# atx4vc.net
KiCad netlist of a schematic drawn in EAGLE
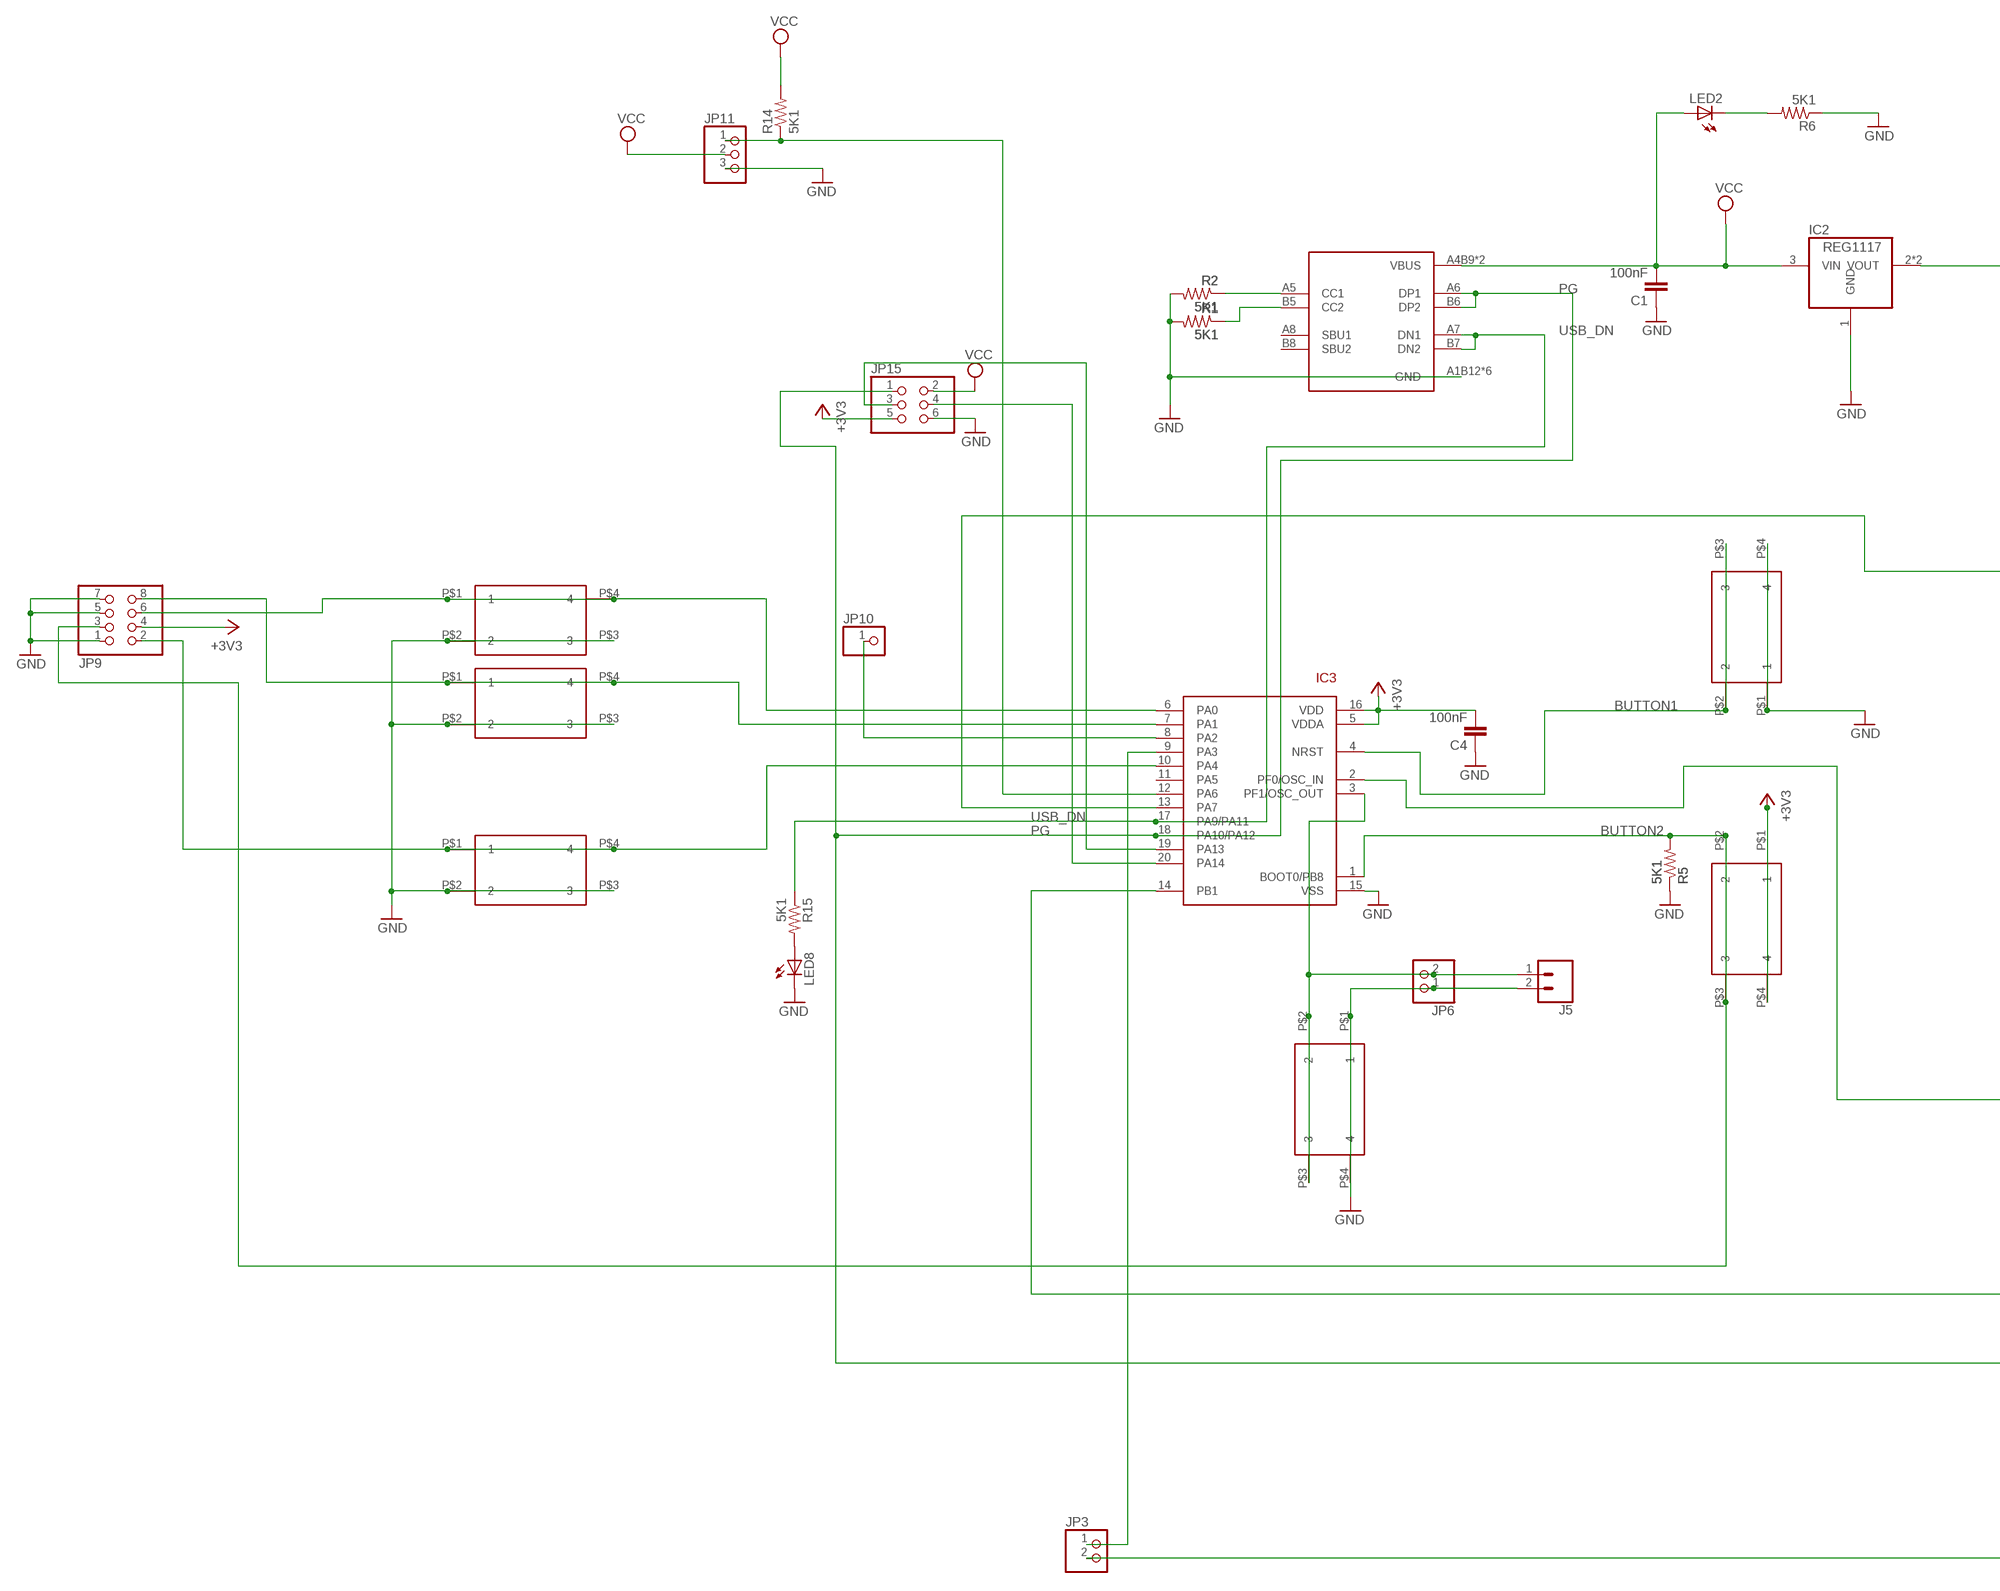
[diagram p0: schematic, sheet 1, part 1 of 2]
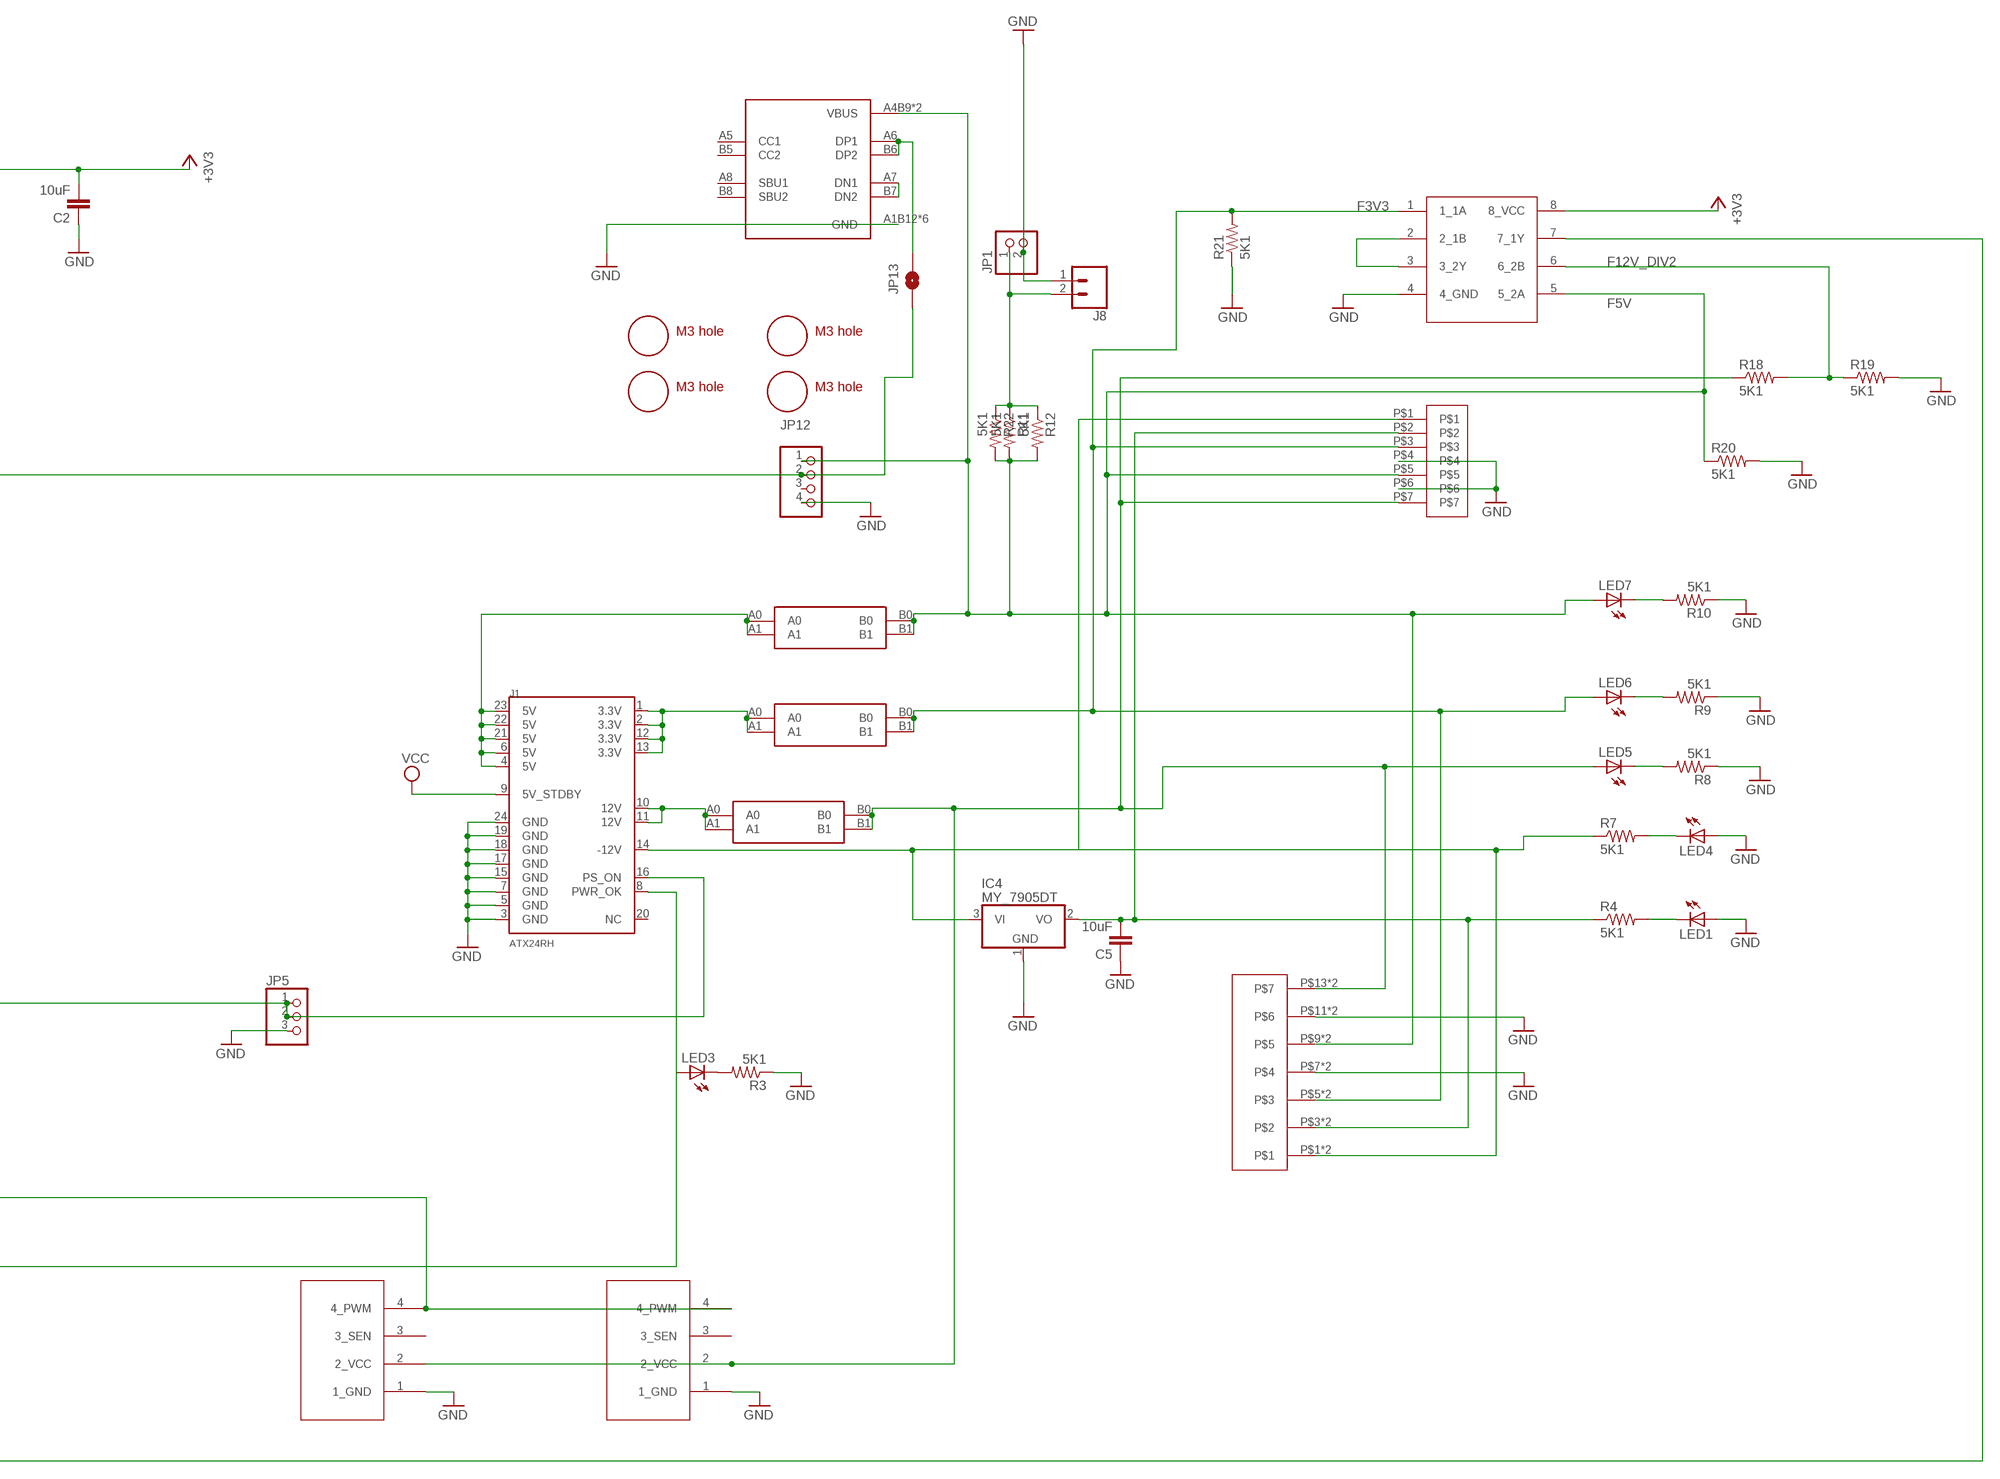
[diagram p1: schematic, sheet 1, part 2 of 2]

(export (version "E")
  (design (tool "Eeschema 10.0.6"))
  (components
    (comp (ref "C1")
      (value "100nF")
      (footprint "eagle-import:0805$1")
      (libsource (lib "eagle-import") (part "CAP0805"))
    )
    (comp (ref "C2")
      (value "10uF")
      (footprint "eagle-import:0805$1")
      (libsource (lib "eagle-import") (part "CAP0805"))
    )
    (comp (ref "C4")
      (value "100nF")
      (footprint "eagle-import:0805$1")
      (libsource (lib "eagle-import") (part "CAP0805"))
    )
    (comp (ref "C5")
      (value "10uF")
      (footprint "eagle-import:0805$1")
      (libsource (lib "eagle-import") (part "CAP0805"))
    )
    (comp (ref "IC2")
      (value "REG1117")
      (footprint "eagle-import:SOT223")
      (fields (field (name "MF") "TEXAS INSTRUMENTS") (field (name "MPN") "REG1117FAKTTT"))
      (libsource (lib "eagle-import") (part "REG1117"))
    )
    (comp (ref "IC3")
      (value "STM32F042F4")
      (footprint "eagle-import:TSSOP20")
      (libsource (lib "eagle-import") (part "STM32F042F4"))
    )
    (comp (ref "IC4")
      (value "MY_7905DT")
      (footprint "eagle-import:ADAFRUIT_TO252")
      (libsource (lib "eagle-import") (part "MY_7905DT"))
    )
    (comp (ref "J1")
      (value "ATX24RH")
      (footprint "eagle-import:ATX24_RIGHT_ANGLE")
      (libsource (lib "eagle-import") (part "ATX24RH"))
    )
    (comp (ref "J5")
      (value "CONN_023.5MM")
      (footprint "eagle-import:SCREWTERMINAL-3.5MM-2")
      (libsource (lib "eagle-import") (part "CONN_023.5MM"))
    )
    (comp (ref "J8")
      (value "CONN_023.5MM")
      (footprint "eagle-import:SCREWTERMINAL-3.5MM-2")
      (libsource (lib "eagle-import") (part "CONN_023.5MM"))
    )
    (comp (ref "JP1")
      (value "PINHD-1X2")
      (footprint "eagle-import:1X02")
      (libsource (lib "eagle-import") (part "pinhead_325_PINHD-1X2"))
    )
    (comp (ref "JP3")
      (value "PINHD-1X2")
      (footprint "eagle-import:1X02")
      (libsource (lib "eagle-import") (part "pinhead_325_PINHD-1X2"))
    )
    (comp (ref "JP5")
      (value "PINHD-1X3:1")
      (footprint "eagle-import:1X03")
      (libsource (lib "eagle-import") (part "PINHD-1X3?{colon}1"))
    )
    (comp (ref "JP6")
      (value "PINHD-1X2")
      (footprint "eagle-import:1X02")
      (libsource (lib "eagle-import") (part "PINHD-1X2"))
    )
    (comp (ref "JP8")
      (value "4PIN_FAN")
      (footprint "eagle-import:1X04")
      (libsource (lib "eagle-import") (part "4PIN_FAN"))
    )
    (comp (ref "JP9")
      (value "PINHD-2X4")
      (footprint "eagle-import:2X04")
      (libsource (lib "eagle-import") (part "PINHD-2X4"))
    )
    (comp (ref "JP10")
      (value "PINHD-1X1CB")
      (footprint "eagle-import:1X01-CLEANBIG")
      (libsource (lib "eagle-import") (part "PINHD-1X1CB"))
    )
    (comp (ref "JP11")
      (value "PINHD-1X3")
      (footprint "eagle-import:1X03")
      (libsource (lib "eagle-import") (part "PINHD-1X3"))
    )
    (comp (ref "JP12")
      (value "PINHD-1X4")
      (footprint "eagle-import:1X04")
      (libsource (lib "eagle-import") (part "PINHD-1X4"))
    )
    (comp (ref "JP13")
      (value "JUMPER-SMT_2_NO_NO-SILK")
      (footprint "eagle-import:SMT-JUMPER_2_NO_NO-SILK")
      (libsource (lib "eagle-import") (part "JUMPER-SMT_2_NO_NO-SILK"))
    )
    (comp (ref "JP15")
      (value "PINHD-2X3")
      (footprint "eagle-import:2X03")
      (libsource (lib "eagle-import") (part "PINHD-2X3"))
    )
    (comp (ref "JP16")
      (value "4PIN_FAN")
      (footprint "eagle-import:1X04")
      (libsource (lib "eagle-import") (part "4PIN_FAN"))
    )
    (comp (ref "LED1")
      (value "LEDCHIP-LED0805")
      (footprint "eagle-import:CHIP-LED0805")
      (libsource (lib "eagle-import") (part "LEDCHIP-LED0805"))
    )
    (comp (ref "LED2")
      (value "LEDCHIP-LED0805")
      (footprint "eagle-import:CHIP-LED0805")
      (libsource (lib "eagle-import") (part "LEDCHIP-LED0805"))
    )
    (comp (ref "LED3")
      (value "LEDCHIP-LED0805")
      (footprint "eagle-import:CHIP-LED0805")
      (libsource (lib "eagle-import") (part "LEDCHIP-LED0805"))
    )
    (comp (ref "LED4")
      (value "LEDCHIP-LED0805")
      (footprint "eagle-import:CHIP-LED0805")
      (libsource (lib "eagle-import") (part "LEDCHIP-LED0805"))
    )
    (comp (ref "LED5")
      (value "LEDCHIP-LED0805")
      (footprint "eagle-import:CHIP-LED0805")
      (libsource (lib "eagle-import") (part "LEDCHIP-LED0805"))
    )
    (comp (ref "LED6")
      (value "LEDCHIP-LED0805")
      (footprint "eagle-import:CHIP-LED0805")
      (libsource (lib "eagle-import") (part "LEDCHIP-LED0805"))
    )
    (comp (ref "LED7")
      (value "LEDCHIP-LED0805")
      (footprint "eagle-import:CHIP-LED0805")
      (libsource (lib "eagle-import") (part "LEDCHIP-LED0805"))
    )
    (comp (ref "LED8")
      (value "LEDCHIP-LED0805")
      (footprint "eagle-import:CHIP-LED0805")
      (libsource (lib "eagle-import") (part "LEDCHIP-LED0805"))
    )
    (comp (ref "R1")
      (value "5K1")
      (footprint "eagle-import:0805")
      (libsource (lib "eagle-import") (part "atx_power_control_RESISTOR0805-RES"))
    )
    (comp (ref "R2")
      (value "5K1")
      (footprint "eagle-import:0805")
      (libsource (lib "eagle-import") (part "atx_power_control_RESISTOR0805-RES"))
    )
    (comp (ref "R3")
      (value "5K1")
      (footprint "eagle-import:0805")
      (libsource (lib "eagle-import") (part "atx_power_control_RESISTOR0805-RES"))
    )
    (comp (ref "R4")
      (value "5K1")
      (footprint "eagle-import:0805")
      (libsource (lib "eagle-import") (part "RESISTOR0805-RES"))
    )
    (comp (ref "R5")
      (value "5K1")
      (footprint "eagle-import:0805")
      (libsource (lib "eagle-import") (part "atx_power_control_RESISTOR0805-RES"))
    )
    (comp (ref "R6")
      (value "5K1")
      (footprint "eagle-import:0805")
      (libsource (lib "eagle-import") (part "atx_power_control_RESISTOR0805-RES"))
    )
    (comp (ref "R7")
      (value "5K1")
      (footprint "eagle-import:0805")
      (libsource (lib "eagle-import") (part "RESISTOR0805-RES"))
    )
    (comp (ref "R8")
      (value "5K1")
      (footprint "eagle-import:0805")
      (libsource (lib "eagle-import") (part "atx_power_control_RESISTOR0805-RES"))
    )
    (comp (ref "R9")
      (value "5K1")
      (footprint "eagle-import:0805")
      (libsource (lib "eagle-import") (part "atx_power_control_RESISTOR0805-RES"))
    )
    (comp (ref "R10")
      (value "5K1")
      (footprint "eagle-import:0805")
      (libsource (lib "eagle-import") (part "atx_power_control_RESISTOR0805-RES"))
    )
    (comp (ref "R11")
      (value "5K1")
      (footprint "eagle-import:0805")
      (libsource (lib "eagle-import") (part "atx_power_control_RESISTOR0805-RES"))
    )
    (comp (ref "R12")
      (value "5K1")
      (footprint "eagle-import:0805")
      (libsource (lib "eagle-import") (part "atx_power_control_RESISTOR0805-RES"))
    )
    (comp (ref "R14")
      (value "5K1")
      (footprint "eagle-import:0805")
      (libsource (lib "eagle-import") (part "atx_power_control_RESISTOR0805-RES"))
    )
    (comp (ref "R15")
      (value "5K1")
      (footprint "eagle-import:0805")
      (libsource (lib "eagle-import") (part "atx_power_control_RESISTOR0805-RES"))
    )
    (comp (ref "R18")
      (value "5K1")
      (footprint "eagle-import:0805")
      (libsource (lib "eagle-import") (part "atx_power_control_RESISTOR0805-RES"))
    )
    (comp (ref "R19")
      (value "5K1")
      (footprint "eagle-import:0805")
      (libsource (lib "eagle-import") (part "atx_power_control_RESISTOR0805-RES"))
    )
    (comp (ref "R20")
      (value "5K1")
      (footprint "eagle-import:0805")
      (libsource (lib "eagle-import") (part "atx_power_control_RESISTOR0805-RES"))
    )
    (comp (ref "R21")
      (value "5K1")
      (footprint "eagle-import:0805")
      (libsource (lib "eagle-import") (part "atx_power_control_RESISTOR0805-RES"))
    )
    (comp (ref "R22")
      (value "5K1")
      (footprint "eagle-import:0805")
      (libsource (lib "eagle-import") (part "atx_power_control_RESISTOR0805-RES"))
    )
    (comp (ref "SW1")
      (value "324_SW")
      (footprint "eagle-import:342_SWICH_FOOT")
      (libsource (lib "eagle-import") (part "324_SW"))
    )
    (comp (ref "SW2")
      (value "324_SW")
      (footprint "eagle-import:342_SWICH_FOOT")
      (libsource (lib "eagle-import") (part "324_SW"))
    )
    (comp (ref "SW3")
      (value "324_SW")
      (footprint "eagle-import:342_SWICH_FOOT")
      (libsource (lib "eagle-import") (part "324_SW"))
    )
    (comp (ref "SW4")
      (value "324_SW")
      (footprint "eagle-import:342_SWICH_FOOT")
      (libsource (lib "eagle-import") (part "324_SW"))
    )
    (comp (ref "SW5")
      (value "324_SW")
      (footprint "eagle-import:342_SWICH_FOOT")
      (libsource (lib "eagle-import") (part "324_SW"))
    )
    (comp (ref "SW7")
      (value "324_SW")
      (footprint "eagle-import:342_SWICH_FOOT")
      (libsource (lib "eagle-import") (part "324_SW"))
    )
    (comp (ref "U$1")
      (value "M3_MOUNTING_HOLE")
      (footprint "eagle-import:M3_MOUNTING_HOLE_PACK")
      (libsource (lib "eagle-import") (part "M3_MOUNTING_HOLE"))
    )
    (comp (ref "U$2")
      (value "M3_MOUNTING_HOLE")
      (footprint "eagle-import:M3_MOUNTING_HOLE_PACK")
      (libsource (lib "eagle-import") (part "M3_MOUNTING_HOLE"))
    )
    (comp (ref "U$3")
      (value "M3_MOUNTING_HOLE")
      (footprint "eagle-import:M3_MOUNTING_HOLE_PACK")
      (libsource (lib "eagle-import") (part "M3_MOUNTING_HOLE"))
    )
    (comp (ref "U$4")
      (value "VH396")
      (footprint "eagle-import:396_7P")
      (libsource (lib "eagle-import") (part "VH396"))
    )
    (comp (ref "U$5")
      (value "CAR_FUSE_HOLDER3IN1")
      (footprint "eagle-import:FUSE_HOLDER_3IN1")
      (libsource (lib "eagle-import") (part "CAR_FUSE_HOLDER3IN1"))
    )
    (comp (ref "U$6")
      (value "74LVC2G08")
      (footprint "eagle-import:VSSOP08")
      (libsource (lib "eagle-import") (part "74LVC2G08"))
    )
    (comp (ref "U$7")
      (value "CAR_FUSE_HOLDER3IN1")
      (footprint "eagle-import:FUSE_HOLDER_3IN1")
      (libsource (lib "eagle-import") (part "CAR_FUSE_HOLDER3IN1"))
    )
    (comp (ref "U$8")
      (value "CAR_FUSE_HOLDER3IN1")
      (footprint "eagle-import:FUSE_HOLDER_3IN1")
      (libsource (lib "eagle-import") (part "CAR_FUSE_HOLDER3IN1"))
    )
    (comp (ref "U$9")
      (value "WAGO257-7")
      (footprint "eagle-import:WAGO257-7")
      (libsource (lib "eagle-import") (part "WAGO257-7"))
    )
    (comp (ref "U$10")
      (value "M3_MOUNTING_HOLE")
      (footprint "eagle-import:M3_MOUNTING_HOLE_PACK")
      (libsource (lib "eagle-import") (part "M3_MOUNTING_HOLE"))
    )
    (comp (ref "U1")
      (value "USBC_16P")
      (footprint "eagle-import:USBC_16P_FOOT")
      (libsource (lib "eagle-import") (part "USBC_16P"))
    )
    (comp (ref "U2")
      (value "USBC_16P")
      (footprint "eagle-import:USBC_16P_FOOT")
      (libsource (lib "eagle-import") (part "USBC_16P"))
    )
  )
  (nets
    (net (code "1") (name "+3V3") (class "Default")
      (node (ref "C2") (pin "2") (pinfunction "2_2") (pintype "passive"))
      (node (ref "C4") (pin "2") (pinfunction "2_2") (pintype "passive"))
      (node (ref "IC2") (pin "2") (pinfunction "VOUT_2") (pintype "output"))
      (node (ref "IC2") (pin "4") (pinfunction "VOUT_4") (pintype "output"))
      (node (ref "IC3") (pin "16") (pinfunction "VDD_16") (pintype "bidirectional"))
      (node (ref "IC3") (pin "5") (pinfunction "VDDA_5") (pintype "bidirectional"))
      (node (ref "JP15") (pin "5") (pinfunction "5_5") (pintype "passive"))
      (node (ref "JP9") (pin "4") (pinfunction "4_4") (pintype "passive"))
      (node (ref "SW4") (pin "P$1") (pinfunction "1_P$1") (pintype "bidirectional"))
      (node (ref "SW4") (pin "P$4") (pinfunction "4_P$4") (pintype "bidirectional"))
      (node (ref "U$6") (pin "8") (pinfunction "8_VCC_8") (pintype "power_in"))
    )
    (net (code "2") (name "/BUTTON1") (class "Default")
      (node (ref "IC3") (pin "4") (pinfunction "NRST_4") (pintype "bidirectional"))
      (node (ref "SW3") (pin "P$2") (pinfunction "2_P$2") (pintype "bidirectional"))
      (node (ref "SW3") (pin "P$3") (pinfunction "3_P$3") (pintype "bidirectional"))
    )
    (net (code "3") (name "/BUTTON2") (class "Default")
      (node (ref "IC3") (pin "1") (pinfunction "BOOT0/PB8_1") (pintype "bidirectional"))
      (node (ref "JP9") (pin "3") (pinfunction "3_3") (pintype "passive"))
      (node (ref "R5") (pin "2") (pinfunction "2_2") (pintype "passive"))
      (node (ref "SW4") (pin "P$2") (pinfunction "2_P$2") (pintype "bidirectional"))
      (node (ref "SW4") (pin "P$3") (pinfunction "3_P$3") (pintype "bidirectional"))
    )
    (net (code "4") (name "/F3V3") (class "Default")
      (node (ref "LED6") (pin "A") (pinfunction "A_A") (pintype "passive"))
      (node (ref "R21") (pin "2") (pinfunction "2_2") (pintype "passive"))
      (node (ref "U$4") (pin "P$3") (pinfunction "P$3_P$3") (pintype "bidirectional"))
      (node (ref "U$6") (pin "1") (pinfunction "1_1A_1") (pintype "power_in"))
      (node (ref "U$7") (pin "B0") (pinfunction "B0_B0") (pintype "bidirectional"))
      (node (ref "U$7") (pin "B1") (pinfunction "B1_B1") (pintype "bidirectional"))
      (node (ref "U$9") (pin "P$5") (pinfunction "P$3_P$5") (pintype "bidirectional"))
      (node (ref "U$9") (pin "P$6") (pinfunction "P$3_P$6") (pintype "bidirectional"))
    )
    (net (code "5") (name "/F5V") (class "Default")
      (node (ref "JP12") (pin "1") (pinfunction "1_1") (pintype "passive"))
      (node (ref "LED7") (pin "A") (pinfunction "A_A") (pintype "passive"))
      (node (ref "R11") (pin "2") (pinfunction "2_2") (pintype "passive"))
      (node (ref "R12") (pin "2") (pinfunction "2_2") (pintype "passive"))
      (node (ref "R20") (pin "1") (pinfunction "1_1") (pintype "passive"))
      (node (ref "R22") (pin "2") (pinfunction "2_2") (pintype "passive"))
      (node (ref "U$4") (pin "P$5") (pinfunction "P$5_P$5") (pintype "bidirectional"))
      (node (ref "U$6") (pin "5") (pinfunction "5_2A_5") (pintype "power_in"))
      (node (ref "U$8") (pin "B0") (pinfunction "B0_B0") (pintype "bidirectional"))
      (node (ref "U$8") (pin "B1") (pinfunction "B1_B1") (pintype "bidirectional"))
      (node (ref "U$9") (pin "P$10") (pinfunction "P$5_P$10") (pintype "bidirectional"))
      (node (ref "U$9") (pin "P$9") (pinfunction "P$5_P$9") (pintype "bidirectional"))
      (node (ref "U1") (pin "A4B9") (pinfunction "VBUS_A4B9") (pintype "bidirectional"))
      (node (ref "U1") (pin "B4A9") (pinfunction "VBUS_B4A9") (pintype "bidirectional"))
    )
    (net (code "6") (name "/F12V_DIV2") (class "Default")
      (node (ref "R18") (pin "2") (pinfunction "2_2") (pintype "passive"))
      (node (ref "R19") (pin "1") (pinfunction "1_1") (pintype "passive"))
      (node (ref "U$6") (pin "6") (pinfunction "6_2B_6") (pintype "power_in"))
    )
    (net (code "7") (name "/PG") (class "Default")
      (node (ref "IC3") (pin "18") (pinfunction "PA10/PA12_18") (pintype "bidirectional"))
      (node (ref "J1") (pin "8") (pinfunction "PWR_OK_8") (pintype "bidirectional"))
      (node (ref "JP15") (pin "1") (pinfunction "1_1") (pintype "passive"))
      (node (ref "LED3") (pin "A") (pinfunction "A_A") (pintype "passive"))
      (node (ref "U2") (pin "A6") (pinfunction "DP1_A6") (pintype "bidirectional"))
      (node (ref "U2") (pin "B6") (pinfunction "DP2_B6") (pintype "bidirectional"))
    )
    (net (code "8") (name "/USB_DN") (class "Default")
      (node (ref "IC3") (pin "17") (pinfunction "PA9/PA11_17") (pintype "bidirectional"))
      (node (ref "R15") (pin "1") (pinfunction "1_1") (pintype "passive"))
      (node (ref "U2") (pin "A7") (pinfunction "DN1_A7") (pintype "bidirectional"))
      (node (ref "U2") (pin "B7") (pinfunction "DN2_B7") (pintype "bidirectional"))
    )
    (net (code "9") (name "GND") (class "Default")
      (node (ref "C1") (pin "1") (pinfunction "1_1") (pintype "passive"))
      (node (ref "C2") (pin "1") (pinfunction "1_1") (pintype "passive"))
      (node (ref "C4") (pin "1") (pinfunction "1_1") (pintype "passive"))
      (node (ref "C5") (pin "1") (pinfunction "1_1") (pintype "passive"))
      (node (ref "IC2") (pin "1") (pinfunction "GND_1") (pintype "power_in"))
      (node (ref "IC3") (pin "15") (pinfunction "VSS_15") (pintype "bidirectional"))
      (node (ref "IC4") (pin "1") (pinfunction "GND_1") (pintype "passive"))
      (node (ref "J1") (pin "15") (pinfunction "GND_15") (pintype "bidirectional"))
      (node (ref "J1") (pin "17") (pinfunction "GND_17") (pintype "bidirectional"))
      (node (ref "J1") (pin "18") (pinfunction "GND_18") (pintype "bidirectional"))
      (node (ref "J1") (pin "19") (pinfunction "GND_19") (pintype "bidirectional"))
      (node (ref "J1") (pin "24") (pinfunction "GND_24") (pintype "bidirectional"))
      (node (ref "J1") (pin "3") (pinfunction "GND_3") (pintype "bidirectional"))
      (node (ref "J1") (pin "5") (pinfunction "GND_5") (pintype "bidirectional"))
      (node (ref "J1") (pin "7") (pinfunction "GND_7") (pintype "bidirectional"))
      (node (ref "J5") (pin "2") (pinfunction "2_2") (pintype "passive"))
      (node (ref "J8") (pin "1") (pinfunction "1_1") (pintype "passive"))
      (node (ref "JP1") (pin "2") (pinfunction "2_2") (pintype "passive"))
      (node (ref "JP11") (pin "3") (pinfunction "3_3") (pintype "passive"))
      (node (ref "JP12") (pin "4") (pinfunction "4_4") (pintype "passive"))
      (node (ref "JP15") (pin "6") (pinfunction "6_6") (pintype "passive"))
      (node (ref "JP16") (pin "1") (pinfunction "1_GND_1") (pintype "passive"))
      (node (ref "JP5") (pin "3") (pinfunction "3_3") (pintype "passive"))
      (node (ref "JP6") (pin "1") (pinfunction "1_1") (pintype "passive"))
      (node (ref "JP8") (pin "1") (pinfunction "1_GND_1") (pintype "passive"))
      (node (ref "JP9") (pin "1") (pinfunction "1_1") (pintype "passive"))
      (node (ref "JP9") (pin "5") (pinfunction "5_5") (pintype "passive"))
      (node (ref "JP9") (pin "7") (pinfunction "7_7") (pintype "passive"))
      (node (ref "LED1") (pin "A") (pinfunction "A_A") (pintype "passive"))
      (node (ref "LED4") (pin "A") (pinfunction "A_A") (pintype "passive"))
      (node (ref "LED8") (pin "C") (pinfunction "C_C") (pintype "passive"))
      (node (ref "R1") (pin "2") (pinfunction "2_2") (pintype "passive"))
      (node (ref "R10") (pin "1") (pinfunction "1_1") (pintype "passive"))
      (node (ref "R19") (pin "2") (pinfunction "2_2") (pintype "passive"))
      (node (ref "R2") (pin "2") (pinfunction "2_2") (pintype "passive"))
      (node (ref "R20") (pin "2") (pinfunction "2_2") (pintype "passive"))
      (node (ref "R21") (pin "1") (pinfunction "1_1") (pintype "passive"))
      (node (ref "R3") (pin "1") (pinfunction "1_1") (pintype "passive"))
      (node (ref "R5") (pin "1") (pinfunction "1_1") (pintype "passive"))
      (node (ref "R6") (pin "1") (pinfunction "1_1") (pintype "passive"))
      (node (ref "R8") (pin "1") (pinfunction "1_1") (pintype "passive"))
      (node (ref "R9") (pin "1") (pinfunction "1_1") (pintype "passive"))
      (node (ref "SW1") (pin "P$1") (pinfunction "1_P$1") (pintype "bidirectional"))
      (node (ref "SW1") (pin "P$4") (pinfunction "4_P$4") (pintype "bidirectional"))
      (node (ref "SW2") (pin "P$2") (pinfunction "2_P$2") (pintype "bidirectional"))
      (node (ref "SW2") (pin "P$3") (pinfunction "3_P$3") (pintype "bidirectional"))
      (node (ref "SW3") (pin "P$1") (pinfunction "1_P$1") (pintype "bidirectional"))
      (node (ref "SW3") (pin "P$4") (pinfunction "4_P$4") (pintype "bidirectional"))
      (node (ref "SW5") (pin "P$2") (pinfunction "2_P$2") (pintype "bidirectional"))
      (node (ref "SW5") (pin "P$3") (pinfunction "3_P$3") (pintype "bidirectional"))
      (node (ref "SW7") (pin "P$2") (pinfunction "2_P$2") (pintype "bidirectional"))
      (node (ref "SW7") (pin "P$3") (pinfunction "3_P$3") (pintype "bidirectional"))
      (node (ref "U$4") (pin "P$4") (pinfunction "P$4_P$4") (pintype "bidirectional"))
      (node (ref "U$4") (pin "P$6") (pinfunction "P$6_P$6") (pintype "bidirectional"))
      (node (ref "U$6") (pin "4") (pinfunction "4_GND_4") (pintype "power_in"))
      (node (ref "U$9") (pin "P$11") (pinfunction "P$6_P$11") (pintype "bidirectional"))
      (node (ref "U$9") (pin "P$12") (pinfunction "P$6_P$12") (pintype "bidirectional"))
      (node (ref "U$9") (pin "P$7") (pinfunction "P$4_P$7") (pintype "bidirectional"))
      (node (ref "U$9") (pin "P$8") (pinfunction "P$4_P$8") (pintype "bidirectional"))
      (node (ref "U1") (pin "A1B12") (pinfunction "GND_A1B12") (pintype "bidirectional"))
      (node (ref "U1") (pin "B11A12") (pinfunction "GND_B11A12") (pintype "bidirectional"))
      (node (ref "U1") (pin "P$13") (pinfunction "GND_P$13") (pintype "bidirectional"))
      (node (ref "U1") (pin "P$14") (pinfunction "GND_P$14") (pintype "bidirectional"))
      (node (ref "U1") (pin "P$15") (pinfunction "GND_P$15") (pintype "bidirectional"))
      (node (ref "U1") (pin "P$16") (pinfunction "GND_P$16") (pintype "bidirectional"))
      (node (ref "U2") (pin "A1B12") (pinfunction "GND_A1B12") (pintype "bidirectional"))
      (node (ref "U2") (pin "B11A12") (pinfunction "GND_B11A12") (pintype "bidirectional"))
      (node (ref "U2") (pin "P$13") (pinfunction "GND_P$13") (pintype "bidirectional"))
      (node (ref "U2") (pin "P$14") (pinfunction "GND_P$14") (pintype "bidirectional"))
      (node (ref "U2") (pin "P$15") (pinfunction "GND_P$15") (pintype "bidirectional"))
      (node (ref "U2") (pin "P$16") (pinfunction "GND_P$16") (pintype "bidirectional"))
    )
    (net (code "10") (name "Net-(IC3-PA0)") (class "Default")
      (node (ref "IC3") (pin "6") (pinfunction "PA0_6") (pintype "bidirectional"))
      (node (ref "JP9") (pin "6") (pinfunction "6_6") (pintype "passive"))
      (node (ref "SW2") (pin "P$1") (pinfunction "1_P$1") (pintype "bidirectional"))
      (node (ref "SW2") (pin "P$4") (pinfunction "4_P$4") (pintype "bidirectional"))
    )
    (net (code "11") (name "Net-(IC3-PA1)") (class "Default")
      (node (ref "IC3") (pin "7") (pinfunction "PA1_7") (pintype "bidirectional"))
      (node (ref "JP9") (pin "8") (pinfunction "8_8") (pintype "passive"))
      (node (ref "SW5") (pin "P$1") (pinfunction "1_P$1") (pintype "bidirectional"))
      (node (ref "SW5") (pin "P$4") (pinfunction "4_P$4") (pintype "bidirectional"))
    )
    (net (code "12") (name "Net-(IC3-PA2)") (class "Default")
      (node (ref "IC3") (pin "8") (pinfunction "PA2_8") (pintype "bidirectional"))
      (node (ref "JP10") (pin "1") (pinfunction "1_1") (pintype "passive"))
    )
    (net (code "13") (name "Net-(IC3-PA3)") (class "Default")
      (node (ref "IC3") (pin "9") (pinfunction "PA3_9") (pintype "bidirectional"))
      (node (ref "JP3") (pin "1") (pinfunction "1_1") (pintype "passive"))
    )
    (net (code "14") (name "Net-(IC3-PA4)") (class "Default")
      (node (ref "IC3") (pin "10") (pinfunction "PA4_10") (pintype "bidirectional"))
      (node (ref "JP9") (pin "2") (pinfunction "2_2") (pintype "passive"))
      (node (ref "SW7") (pin "P$1") (pinfunction "1_P$1") (pintype "bidirectional"))
      (node (ref "SW7") (pin "P$4") (pinfunction "4_P$4") (pintype "bidirectional"))
    )
    (net (code "15") (name "Net-(IC3-PA6)") (class "Default")
      (node (ref "IC3") (pin "12") (pinfunction "PA6_12") (pintype "bidirectional"))
      (node (ref "JP11") (pin "1") (pinfunction "1_1") (pintype "passive"))
      (node (ref "R14") (pin "1") (pinfunction "1_1") (pintype "passive"))
    )
    (net (code "16") (name "Net-(IC3-PA7)") (class "Default")
      (node (ref "IC3") (pin "13") (pinfunction "PA7_13") (pintype "bidirectional"))
      (node (ref "JP12") (pin "2") (pinfunction "2_2") (pintype "passive"))
      (node (ref "JP13") (pin "1") (pinfunction "1_1") (pintype "passive"))
    )
    (net (code "17") (name "Net-(IC3-PA13)") (class "Default")
      (node (ref "IC3") (pin "19") (pinfunction "PA13_19") (pintype "bidirectional"))
      (node (ref "JP15") (pin "3") (pinfunction "3_3") (pintype "passive"))
    )
    (net (code "18") (name "Net-(IC3-PA14)") (class "Default")
      (node (ref "IC3") (pin "20") (pinfunction "PA14_20") (pintype "bidirectional"))
      (node (ref "JP15") (pin "4") (pinfunction "4_4") (pintype "passive"))
    )
    (net (code "19") (name "Net-(IC3-PB1)") (class "Default")
      (node (ref "IC3") (pin "14") (pinfunction "PB1_14") (pintype "bidirectional"))
      (node (ref "JP16") (pin "4") (pinfunction "4_PWM_4") (pintype "passive"))
      (node (ref "JP8") (pin "4") (pinfunction "4_PWM_4") (pintype "passive"))
    )
    (net (code "20") (name "Net-(IC3-PF0{slash}OSC_IN)") (class "Default")
      (node (ref "IC3") (pin "2") (pinfunction "PF0/OSC_IN_2") (pintype "bidirectional"))
      (node (ref "J1") (pin "16") (pinfunction "PS_ON_16") (pintype "bidirectional"))
      (node (ref "JP5") (pin "1") (pinfunction "1_1") (pintype "passive"))
      (node (ref "JP5") (pin "2") (pinfunction "2_2") (pintype "passive"))
    )
    (net (code "21") (name "Net-(IC3-PF1{slash}OSC_OUT)") (class "Default")
      (node (ref "IC3") (pin "3") (pinfunction "PF1/OSC_OUT_3") (pintype "bidirectional"))
      (node (ref "J5") (pin "1") (pinfunction "1_1") (pintype "passive"))
      (node (ref "JP6") (pin "2") (pinfunction "2_2") (pintype "passive"))
      (node (ref "SW1") (pin "P$2") (pinfunction "2_P$2") (pintype "bidirectional"))
      (node (ref "SW1") (pin "P$3") (pinfunction "3_P$3") (pintype "bidirectional"))
    )
    (net (code "22") (name "Net-(IC4-VI)") (class "Default")
      (node (ref "IC4") (pin "3") (pinfunction "VI_3") (pintype "input"))
      (node (ref "J1") (pin "14") (pinfunction "-12V_14") (pintype "bidirectional"))
      (node (ref "R7") (pin "1") (pinfunction "1_1") (pintype "passive"))
      (node (ref "U$4") (pin "P$1") (pinfunction "P$1_P$1") (pintype "bidirectional"))
      (node (ref "U$9") (pin "P$1") (pinfunction "P$1_P$1") (pintype "bidirectional"))
      (node (ref "U$9") (pin "P$2") (pinfunction "P$1_P$2") (pintype "bidirectional"))
    )
    (net (code "23") (name "Net-(IC4-VO)") (class "Default")
      (node (ref "C5") (pin "2") (pinfunction "2_2") (pintype "passive"))
      (node (ref "IC4") (pin "2") (pinfunction "VO_2") (pintype "passive"))
      (node (ref "R4") (pin "1") (pinfunction "1_1") (pintype "passive"))
      (node (ref "U$4") (pin "P$2") (pinfunction "P$2_P$2") (pintype "bidirectional"))
      (node (ref "U$9") (pin "P$3") (pinfunction "P$2_P$3") (pintype "bidirectional"))
      (node (ref "U$9") (pin "P$4") (pinfunction "P$2_P$4") (pintype "bidirectional"))
    )
    (net (code "24") (name "Net-(J1-3.3V-Pad1)") (class "Default")
      (node (ref "J1") (pin "1") (pinfunction "3.3V_1") (pintype "bidirectional"))
      (node (ref "J1") (pin "12") (pinfunction "3.3V_12") (pintype "bidirectional"))
      (node (ref "J1") (pin "13") (pinfunction "3.3V_13") (pintype "bidirectional"))
      (node (ref "J1") (pin "2") (pinfunction "3.3V_2") (pintype "bidirectional"))
      (node (ref "U$7") (pin "A0") (pinfunction "A0_A0") (pintype "bidirectional"))
      (node (ref "U$7") (pin "A1") (pinfunction "A1_A1") (pintype "bidirectional"))
    )
    (net (code "25") (name "Net-(J1-5V-Pad21)") (class "Default")
      (node (ref "J1") (pin "21") (pinfunction "5V_21") (pintype "bidirectional"))
      (node (ref "J1") (pin "22") (pinfunction "5V_22") (pintype "bidirectional"))
      (node (ref "J1") (pin "23") (pinfunction "5V_23") (pintype "bidirectional"))
      (node (ref "J1") (pin "4") (pinfunction "5V_4") (pintype "bidirectional"))
      (node (ref "J1") (pin "6") (pinfunction "5V_6") (pintype "bidirectional"))
      (node (ref "U$8") (pin "A0") (pinfunction "A0_A0") (pintype "bidirectional"))
      (node (ref "U$8") (pin "A1") (pinfunction "A1_A1") (pintype "bidirectional"))
    )
    (net (code "26") (name "Net-(J1-12V-Pad10)") (class "Default")
      (node (ref "J1") (pin "10") (pinfunction "12V_10") (pintype "bidirectional"))
      (node (ref "J1") (pin "11") (pinfunction "12V_11") (pintype "bidirectional"))
      (node (ref "U$5") (pin "A0") (pinfunction "A0_A0") (pintype "bidirectional"))
      (node (ref "U$5") (pin "A1") (pinfunction "A1_A1") (pintype "bidirectional"))
    )
    (net (code "27") (name "Net-(J8-Pad2)") (class "Default")
      (node (ref "J8") (pin "2") (pinfunction "2_2") (pintype "passive"))
      (node (ref "JP1") (pin "1") (pinfunction "1_1") (pintype "passive"))
      (node (ref "R11") (pin "1") (pinfunction "1_1") (pintype "passive"))
      (node (ref "R12") (pin "1") (pinfunction "1_1") (pintype "passive"))
      (node (ref "R22") (pin "1") (pinfunction "1_1") (pintype "passive"))
    )
    (net (code "28") (name "Net-(JP16-2_VCC)") (class "Default")
      (node (ref "JP16") (pin "2") (pinfunction "2_VCC_2") (pintype "passive"))
      (node (ref "JP8") (pin "2") (pinfunction "2_VCC_2") (pintype "passive"))
      (node (ref "LED5") (pin "A") (pinfunction "A_A") (pintype "passive"))
      (node (ref "R18") (pin "1") (pinfunction "1_1") (pintype "passive"))
      (node (ref "U$4") (pin "P$7") (pinfunction "P$7_P$7") (pintype "bidirectional"))
      (node (ref "U$5") (pin "B0") (pinfunction "B0_B0") (pintype "bidirectional"))
      (node (ref "U$5") (pin "B1") (pinfunction "B1_B1") (pintype "bidirectional"))
      (node (ref "U$9") (pin "P$13") (pinfunction "P$7_P$13") (pintype "bidirectional"))
      (node (ref "U$9") (pin "P$14") (pinfunction "P$7_P$14") (pintype "bidirectional"))
    )
    (net (code "29") (name "Net-(LED1-PadC)") (class "Default")
      (node (ref "LED1") (pin "C") (pinfunction "C_C") (pintype "passive"))
      (node (ref "R4") (pin "2") (pinfunction "2_2") (pintype "passive"))
    )
    (net (code "30") (name "Net-(LED2-PadC)") (class "Default")
      (node (ref "LED2") (pin "C") (pinfunction "C_C") (pintype "passive"))
      (node (ref "R6") (pin "2") (pinfunction "2_2") (pintype "passive"))
    )
    (net (code "31") (name "Net-(LED3-PadC)") (class "Default")
      (node (ref "LED3") (pin "C") (pinfunction "C_C") (pintype "passive"))
      (node (ref "R3") (pin "2") (pinfunction "2_2") (pintype "passive"))
    )
    (net (code "32") (name "Net-(LED4-PadC)") (class "Default")
      (node (ref "LED4") (pin "C") (pinfunction "C_C") (pintype "passive"))
      (node (ref "R7") (pin "2") (pinfunction "2_2") (pintype "passive"))
    )
    (net (code "33") (name "Net-(LED5-PadC)") (class "Default")
      (node (ref "LED5") (pin "C") (pinfunction "C_C") (pintype "passive"))
      (node (ref "R8") (pin "2") (pinfunction "2_2") (pintype "passive"))
    )
    (net (code "34") (name "Net-(LED6-PadC)") (class "Default")
      (node (ref "LED6") (pin "C") (pinfunction "C_C") (pintype "passive"))
      (node (ref "R9") (pin "2") (pinfunction "2_2") (pintype "passive"))
    )
    (net (code "35") (name "Net-(LED7-PadC)") (class "Default")
      (node (ref "LED7") (pin "C") (pinfunction "C_C") (pintype "passive"))
      (node (ref "R10") (pin "2") (pinfunction "2_2") (pintype "passive"))
    )
    (net (code "36") (name "Net-(LED8-PadA)") (class "Default")
      (node (ref "LED8") (pin "A") (pinfunction "A_A") (pintype "passive"))
      (node (ref "R15") (pin "2") (pinfunction "2_2") (pintype "passive"))
    )
    (net (code "37") (name "Net-(U$6-2_1B)") (class "Default")
      (node (ref "U$6") (pin "2") (pinfunction "2_1B_2") (pintype "power_in"))
      (node (ref "U$6") (pin "3") (pinfunction "3_2Y_3") (pintype "power_in"))
    )
    (net (code "38") (name "Net-(U$6-7_1Y)") (class "Default")
      (node (ref "JP3") (pin "2") (pinfunction "2_2") (pintype "passive"))
      (node (ref "U$6") (pin "7") (pinfunction "7_1Y_7") (pintype "power_in"))
    )
    (net (code "39") (name "Net-(U1-DN1)") (class "Default")
      (node (ref "U1") (pin "A7") (pinfunction "DN1_A7") (pintype "bidirectional"))
      (node (ref "U1") (pin "B7") (pinfunction "DN2_B7") (pintype "bidirectional"))
    )
    (net (code "40") (name "Net-(U1-DP1)") (class "Default")
      (node (ref "JP13") (pin "2") (pinfunction "2_2") (pintype "passive"))
      (node (ref "U1") (pin "A6") (pinfunction "DP1_A6") (pintype "bidirectional"))
      (node (ref "U1") (pin "B6") (pinfunction "DP2_B6") (pintype "bidirectional"))
    )
    (net (code "41") (name "Net-(U2-CC1)") (class "Default")
      (node (ref "R2") (pin "1") (pinfunction "1_1") (pintype "passive"))
      (node (ref "U2") (pin "A5") (pinfunction "CC1_A5") (pintype "bidirectional"))
    )
    (net (code "42") (name "Net-(U2-CC2)") (class "Default")
      (node (ref "R1") (pin "1") (pinfunction "1_1") (pintype "passive"))
      (node (ref "U2") (pin "B5") (pinfunction "CC2_B5") (pintype "bidirectional"))
    )
    (net (code "43") (name "VCC") (class "Default")
      (node (ref "C1") (pin "2") (pinfunction "2_2") (pintype "passive"))
      (node (ref "IC2") (pin "3") (pinfunction "VIN_3") (pintype "input"))
      (node (ref "J1") (pin "9") (pinfunction "5V_STDBY_9") (pintype "bidirectional"))
      (node (ref "JP11") (pin "2") (pinfunction "2_2") (pintype "passive"))
      (node (ref "JP15") (pin "2") (pinfunction "2_2") (pintype "passive"))
      (node (ref "LED2") (pin "A") (pinfunction "A_A") (pintype "passive"))
      (node (ref "R14") (pin "2") (pinfunction "2_2") (pintype "passive"))
      (node (ref "U2") (pin "A4B9") (pinfunction "VBUS_A4B9") (pintype "bidirectional"))
      (node (ref "U2") (pin "B4A9") (pinfunction "VBUS_B4A9") (pintype "bidirectional"))
    )
    (net (code "44") (name "unconnected-(IC3-PA5-Pad11)") (class "Default")
      (node (ref "IC3") (pin "11") (pinfunction "PA5_11") (pintype "bidirectional"))
    )
    (net (code "45") (name "unconnected-(J1-NC-Pad20)") (class "Default")
      (node (ref "J1") (pin "20") (pinfunction "NC_20") (pintype "bidirectional"))
    )
    (net (code "46") (name "unconnected-(JP8-3_SEN-Pad3)") (class "Default")
      (node (ref "JP8") (pin "3") (pinfunction "3_SEN_3") (pintype "passive"))
    )
    (net (code "47") (name "unconnected-(JP12-Pad3)") (class "Default")
      (node (ref "JP12") (pin "3") (pinfunction "3_3") (pintype "passive"))
    )
    (net (code "48") (name "unconnected-(JP16-3_SEN-Pad3)") (class "Default")
      (node (ref "JP16") (pin "3") (pinfunction "3_SEN_3") (pintype "passive"))
    )
    (net (code "49") (name "unconnected-(U1-CC1-PadA5)") (class "Default")
      (node (ref "U1") (pin "A5") (pinfunction "CC1_A5") (pintype "bidirectional"))
    )
    (net (code "50") (name "unconnected-(U1-CC2-PadB5)") (class "Default")
      (node (ref "U1") (pin "B5") (pinfunction "CC2_B5") (pintype "bidirectional"))
    )
    (net (code "51") (name "unconnected-(U1-SBU1-PadA8)") (class "Default")
      (node (ref "U1") (pin "A8") (pinfunction "SBU1_A8") (pintype "bidirectional"))
    )
    (net (code "52") (name "unconnected-(U1-SBU2-PadB8)") (class "Default")
      (node (ref "U1") (pin "B8") (pinfunction "SBU2_B8") (pintype "bidirectional"))
    )
    (net (code "53") (name "unconnected-(U2-SBU1-PadA8)") (class "Default")
      (node (ref "U2") (pin "A8") (pinfunction "SBU1_A8") (pintype "bidirectional"))
    )
    (net (code "54") (name "unconnected-(U2-SBU2-PadB8)") (class "Default")
      (node (ref "U2") (pin "B8") (pinfunction "SBU2_B8") (pintype "bidirectional"))
    )
  )
)
